# SmartSteirs_Base.net
KiCad netlist of a schematic drawn in EAGLE
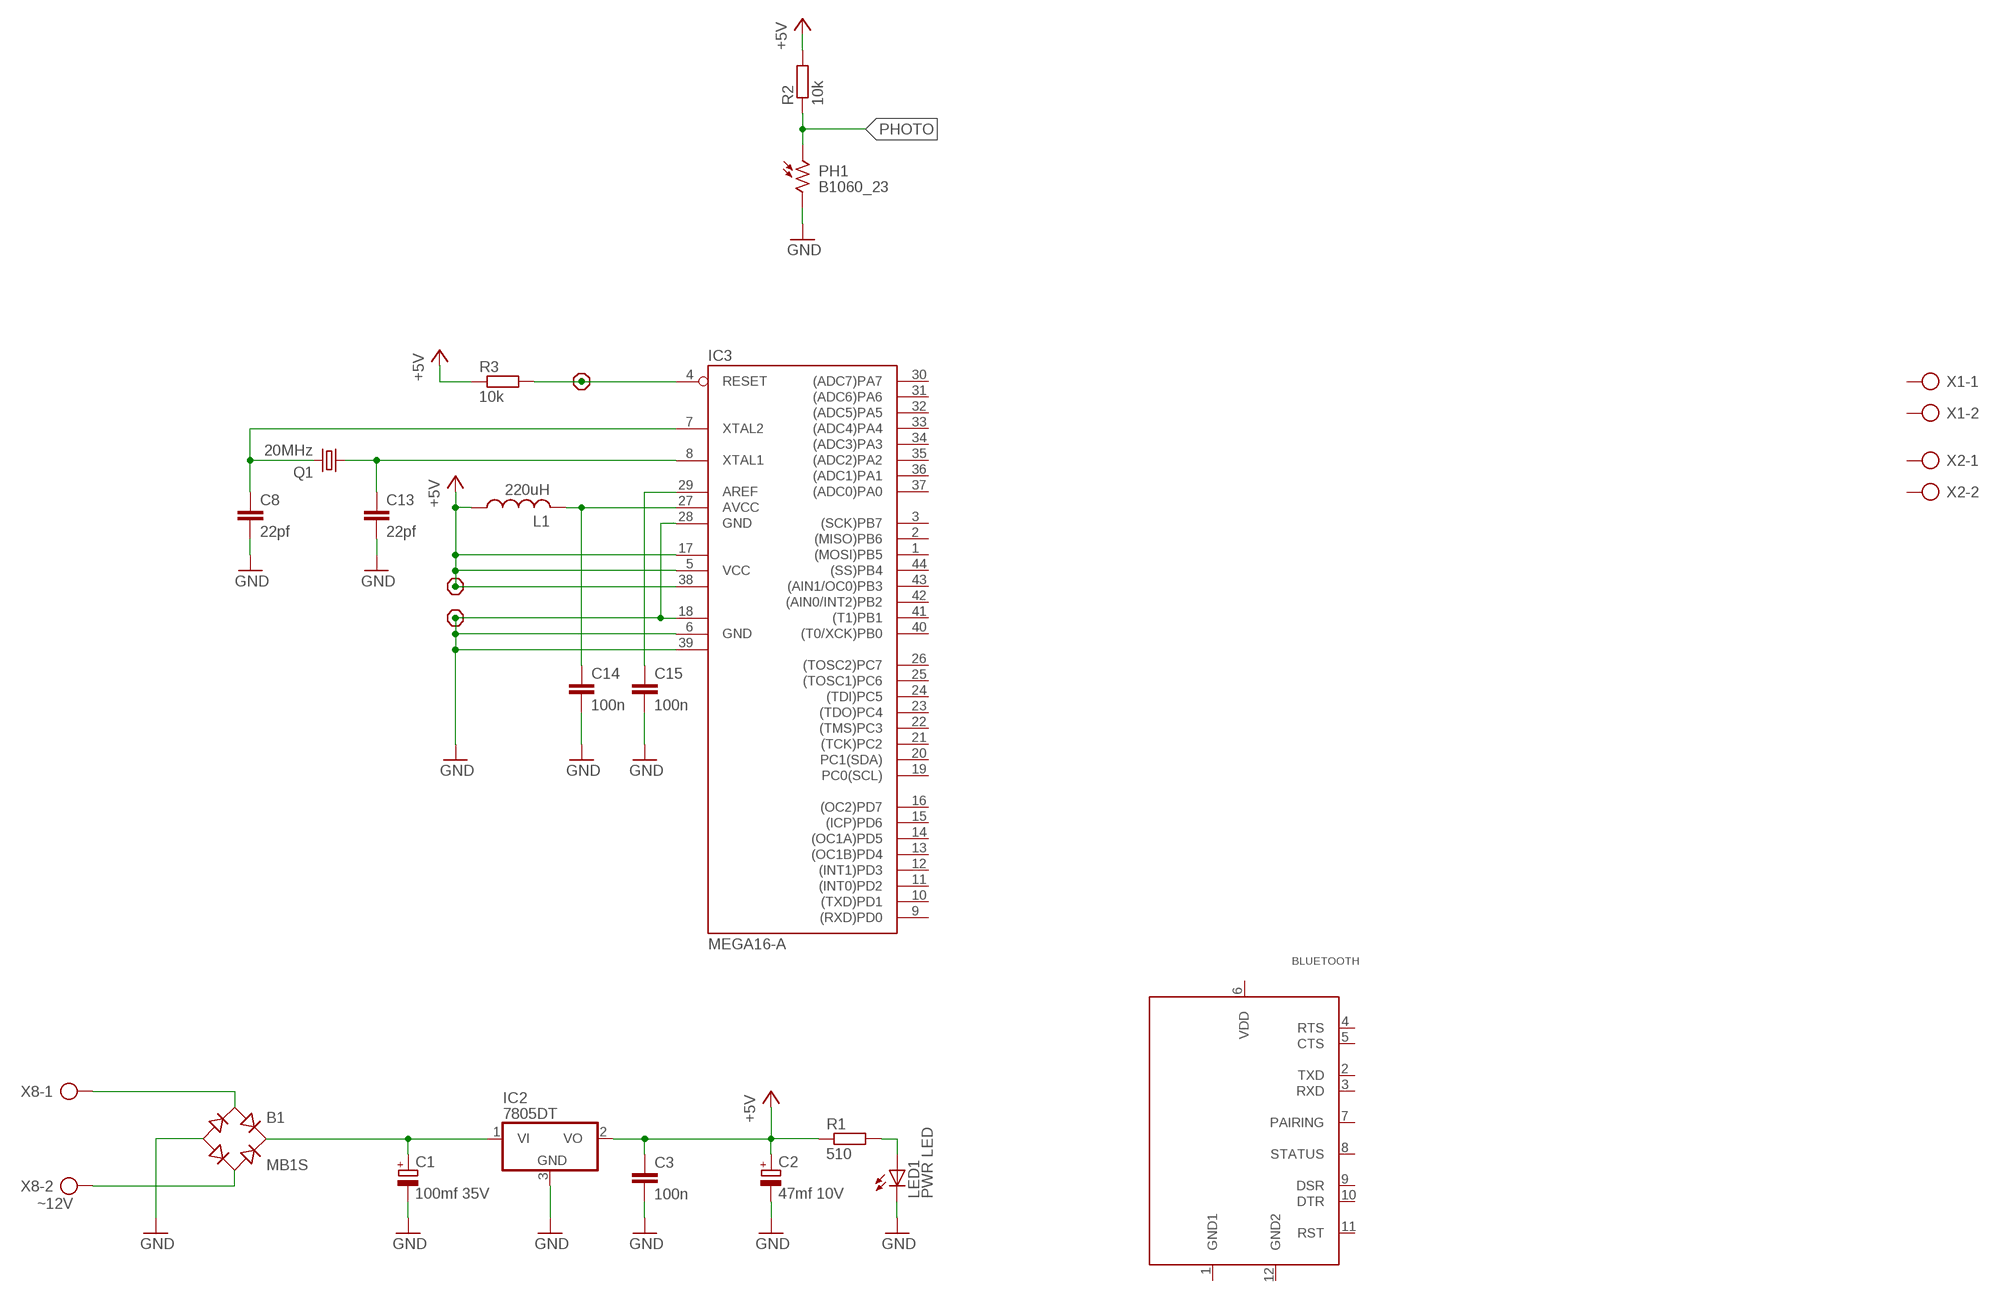
[diagram p0: schematic, sheet 1]

(export (version "E")
  (design (tool "Eeschema 10.0.6"))
  (components
    (comp (ref "B1")
      (value "MB1S")
      (footprint "eagle-import:SOIC-4")
      (libsource (lib "eagle-import") (part "MBS1"))
    )
    (comp (ref "BLUETOOTH")
      (value "ESD110ESD110")
      (footprint "eagle-import:ESD110")
      (libsource (lib "eagle-import") (part "ESD110ESD110"))
    )
    (comp (ref "C1")
      (value "100mf 35V")
      (footprint "eagle-import:E2,5-6")
      (libsource (lib "eagle-import") (part "CPOL-EUE2.5-6"))
    )
    (comp (ref "C2")
      (value "47mf 10V")
      (footprint "eagle-import:E2,5-6")
      (libsource (lib "eagle-import") (part "CPOL-EUE2.5-6"))
    )
    (comp (ref "C3")
      (value "100n")
      (footprint "eagle-import:C0805")
      (libsource (lib "eagle-import") (part "C-EUC0805"))
    )
    (comp (ref "C8")
      (value "22pf")
      (footprint "eagle-import:C0805")
      (libsource (lib "eagle-import") (part "C-EUC0805"))
    )
    (comp (ref "C13")
      (value "22pf")
      (footprint "eagle-import:C0805")
      (libsource (lib "eagle-import") (part "C-EUC0805"))
    )
    (comp (ref "C14")
      (value "100n")
      (footprint "eagle-import:C0805")
      (libsource (lib "eagle-import") (part "C-EUC0805"))
    )
    (comp (ref "C15")
      (value "100n")
      (footprint "eagle-import:C0805")
      (libsource (lib "eagle-import") (part "C-EUC0805"))
    )
    (comp (ref "IC2")
      (value "7805DT")
      (footprint "eagle-import:TO252")
      (libsource (lib "eagle-import") (part "78DT05"))
    )
    (comp (ref "IC3")
      (value "MEGA16-A")
      (footprint "eagle-import:TQFP44")
      (fields (field (name "MPN") "ATMEGA16-16AU"))
      (libsource (lib "eagle-import") (part "MEGA16-A"))
    )
    (comp (ref "JP13")
      (value "PIN_1")
      (footprint "eagle-import:1X01")
      (libsource (lib "eagle-import") (part "PIN_1"))
    )
    (comp (ref "JP14")
      (value "PIN_1")
      (footprint "eagle-import:1X01")
      (libsource (lib "eagle-import") (part "PIN_1"))
    )
    (comp (ref "JP15")
      (value "PIN_1")
      (footprint "eagle-import:1X01")
      (libsource (lib "eagle-import") (part "PIN_1"))
    )
    (comp (ref "L1")
      (value "220uH")
      (footprint "eagle-import:0207_5V")
      (libsource (lib "eagle-import") (part "L-US0207/5V"))
    )
    (comp (ref "LED1")
      (value "PWR LED")
      (footprint "eagle-import:LED3MM")
      (libsource (lib "eagle-import") (part "LED3MM"))
    )
    (comp (ref "PH1")
      (value "B1060_23")
      (footprint "eagle-import:TO-8_B10")
      (libsource (lib "eagle-import") (part "?1060B_23"))
    )
    (comp (ref "Q1")
      (value "20MHz")
      (footprint "eagle-import:HC49_S")
      (libsource (lib "eagle-import") (part "CRYSTALHC49S"))
    )
    (comp (ref "R1")
      (value "510")
      (footprint "eagle-import:M0805")
      (libsource (lib "eagle-import") (part "R-EU_M0805"))
    )
    (comp (ref "R2")
      (value "10k")
      (footprint "eagle-import:M0805")
      (libsource (lib "eagle-import") (part "R-EU_M0805"))
    )
    (comp (ref "R3")
      (value "10k")
      (footprint "eagle-import:M0805")
      (libsource (lib "eagle-import") (part "R-EU_M0805"))
    )
    (comp (ref "X1")
      (value "AK500/2")
      (footprint "eagle-import:AK500_2")
      (libsource (lib "eagle-import") (part "AK500/2"))
    )
    (comp (ref "X2")
      (value "AK500/2")
      (footprint "eagle-import:AK500_2")
      (libsource (lib "eagle-import") (part "AK500/2"))
    )
    (comp (ref "X8")
      (value "~12V")
      (footprint "eagle-import:AK500_2")
      (fields (field (name "OC_FARNELL") "unknown") (field (name "OC_NEWARK") "unknown"))
      (libsource (lib "eagle-import") (part "AK500/2"))
    )
  )
  (nets
    (net (code "1") (name "+5V") (class "Default")
      (node (ref "C2") (pin "+") (pinfunction "+_+") (pintype "passive"))
      (node (ref "C3") (pin "1") (pinfunction "1_1") (pintype "passive"))
      (node (ref "IC2") (pin "2") (pinfunction "VO_2") (pintype "passive"))
      (node (ref "IC3") (pin "17") (pinfunction "VCC1_17") (pintype "power_in"))
      (node (ref "IC3") (pin "38") (pinfunction "VCC2_38") (pintype "power_in"))
      (node (ref "IC3") (pin "5") (pinfunction "VCC_5") (pintype "power_in"))
      (node (ref "JP15") (pin "1") (pinfunction "P$1_1") (pintype "bidirectional"))
      (node (ref "L1") (pin "1") (pinfunction "1_1") (pintype "passive"))
      (node (ref "R1") (pin "1") (pinfunction "1_1") (pintype "passive"))
      (node (ref "R2") (pin "2") (pinfunction "2_2") (pintype "passive"))
      (node (ref "R3") (pin "1") (pinfunction "1_1") (pintype "passive"))
    )
    (net (code "2") (name "GND") (class "Default")
      (node (ref "B1") (pin "-") (pinfunction "-_-") (pintype "passive"))
      (node (ref "C1") (pin "-") (pinfunction "-_-") (pintype "passive"))
      (node (ref "C13") (pin "2") (pinfunction "2_2") (pintype "passive"))
      (node (ref "C14") (pin "2") (pinfunction "2_2") (pintype "passive"))
      (node (ref "C15") (pin "2") (pinfunction "2_2") (pintype "passive"))
      (node (ref "C2") (pin "-") (pinfunction "-_-") (pintype "passive"))
      (node (ref "C3") (pin "2") (pinfunction "2_2") (pintype "passive"))
      (node (ref "C8") (pin "2") (pinfunction "2_2") (pintype "passive"))
      (node (ref "IC2") (pin "3") (pinfunction "GND_3") (pintype "passive"))
      (node (ref "IC3") (pin "18") (pinfunction "GND1_18") (pintype "power_in"))
      (node (ref "IC3") (pin "28") (pinfunction "GND_28") (pintype "power_in"))
      (node (ref "IC3") (pin "39") (pinfunction "GND2_39") (pintype "power_in"))
      (node (ref "IC3") (pin "6") (pinfunction "GND_6") (pintype "power_in"))
      (node (ref "JP14") (pin "1") (pinfunction "P$1_1") (pintype "bidirectional"))
      (node (ref "LED1") (pin "K") (pinfunction "C_K") (pintype "passive"))
      (node (ref "PH1") (pin "2") (pinfunction "2_2") (pintype "passive"))
    )
    (net (code "3") (name "Net-(B1-AC1)") (class "Default")
      (node (ref "B1") (pin "~1") (pinfunction "AC1_~1") (pintype "passive"))
      (node (ref "X8") (pin "1") (pinfunction "KL_1") (pintype "passive"))
    )
    (net (code "4") (name "Net-(B1-AC2)") (class "Default")
      (node (ref "B1") (pin "~2") (pinfunction "AC2_~2") (pintype "passive"))
      (node (ref "X8") (pin "2") (pinfunction "KL_2") (pintype "passive"))
    )
    (net (code "5") (name "Net-(IC2-VI)") (class "Default")
      (node (ref "B1") (pin "+") (pinfunction "+_+") (pintype "passive"))
      (node (ref "C1") (pin "+") (pinfunction "+_+") (pintype "passive"))
      (node (ref "IC2") (pin "1") (pinfunction "VI_1") (pintype "input"))
    )
    (net (code "6") (name "Net-(IC3-AREF)") (class "Default")
      (node (ref "C15") (pin "1") (pinfunction "1_1") (pintype "passive"))
      (node (ref "IC3") (pin "29") (pinfunction "AREF_29") (pintype "passive"))
    )
    (net (code "7") (name "Net-(IC3-AVCC)") (class "Default")
      (node (ref "C14") (pin "1") (pinfunction "1_1") (pintype "passive"))
      (node (ref "IC3") (pin "27") (pinfunction "AVCC_27") (pintype "power_in"))
      (node (ref "L1") (pin "2") (pinfunction "2_2") (pintype "passive"))
    )
    (net (code "8") (name "Net-(IC3-RESET)") (class "Default")
      (node (ref "IC3") (pin "4") (pinfunction "RESET_4") (pintype "input"))
      (node (ref "JP13") (pin "1") (pinfunction "P$1_1") (pintype "bidirectional"))
      (node (ref "R3") (pin "2") (pinfunction "2_2") (pintype "passive"))
    )
    (net (code "9") (name "Net-(IC3-XTAL1)") (class "Default")
      (node (ref "C13") (pin "1") (pinfunction "1_1") (pintype "passive"))
      (node (ref "IC3") (pin "8") (pinfunction "XTAL1_8") (pintype "bidirectional"))
      (node (ref "Q1") (pin "1") (pinfunction "1_1") (pintype "passive"))
    )
    (net (code "10") (name "Net-(IC3-XTAL2)") (class "Default")
      (node (ref "C8") (pin "1") (pinfunction "1_1") (pintype "passive"))
      (node (ref "IC3") (pin "7") (pinfunction "XTAL2_7") (pintype "bidirectional"))
      (node (ref "Q1") (pin "2") (pinfunction "2_2") (pintype "passive"))
    )
    (net (code "11") (name "Net-(LED1-PadA)") (class "Default")
      (node (ref "LED1") (pin "A") (pinfunction "A_A") (pintype "passive"))
      (node (ref "R1") (pin "2") (pinfunction "2_2") (pintype "passive"))
    )
    (net (code "12") (name "PHOTO") (class "Default")
      (node (ref "PH1") (pin "1") (pinfunction "1_1") (pintype "passive"))
      (node (ref "R2") (pin "1") (pinfunction "1_1") (pintype "passive"))
    )
    (net (code "13") (name "unconnected-(BLUETOOTH-CTS-Pad5)") (class "Default")
      (node (ref "BLUETOOTH") (pin "5") (pinfunction "CTS_5") (pintype "passive"))
    )
    (net (code "14") (name "unconnected-(BLUETOOTH-DSR-Pad9)") (class "Default")
      (node (ref "BLUETOOTH") (pin "9") (pinfunction "DSR_9") (pintype "passive"))
    )
    (net (code "15") (name "unconnected-(BLUETOOTH-DTR-Pad10)") (class "Default")
      (node (ref "BLUETOOTH") (pin "10") (pinfunction "DTR_10") (pintype "passive"))
    )
    (net (code "16") (name "unconnected-(BLUETOOTH-GND1-Pad1)") (class "Default")
      (node (ref "BLUETOOTH") (pin "1") (pinfunction "GND1_1") (pintype "passive"))
    )
    (net (code "17") (name "unconnected-(BLUETOOTH-GND2-Pad12)") (class "Default")
      (node (ref "BLUETOOTH") (pin "12") (pinfunction "GND2_12") (pintype "passive"))
    )
    (net (code "18") (name "unconnected-(BLUETOOTH-PAIRING-Pad7)") (class "Default")
      (node (ref "BLUETOOTH") (pin "7") (pinfunction "PAIRING_7") (pintype "passive"))
    )
    (net (code "19") (name "unconnected-(BLUETOOTH-RST-Pad11)") (class "Default")
      (node (ref "BLUETOOTH") (pin "11") (pinfunction "RST_11") (pintype "passive"))
    )
    (net (code "20") (name "unconnected-(BLUETOOTH-RTS-Pad4)") (class "Default")
      (node (ref "BLUETOOTH") (pin "4") (pinfunction "RTS_4") (pintype "passive"))
    )
    (net (code "21") (name "unconnected-(BLUETOOTH-RXD-Pad3)") (class "Default")
      (node (ref "BLUETOOTH") (pin "3") (pinfunction "RXD_3") (pintype "passive"))
    )
    (net (code "22") (name "unconnected-(BLUETOOTH-STATUS-Pad8)") (class "Default")
      (node (ref "BLUETOOTH") (pin "8") (pinfunction "STATUS_8") (pintype "passive"))
    )
    (net (code "23") (name "unconnected-(BLUETOOTH-TXD-Pad2)") (class "Default")
      (node (ref "BLUETOOTH") (pin "2") (pinfunction "TXD_2") (pintype "passive"))
    )
    (net (code "24") (name "unconnected-(BLUETOOTH-VDD-Pad6)") (class "Default")
      (node (ref "BLUETOOTH") (pin "6") (pinfunction "VDD_6") (pintype "passive"))
    )
    (net (code "25") (name "unconnected-(IC3-(ADC0)PA0-Pad37)") (class "Default")
      (node (ref "IC3") (pin "37") (pinfunction "(ADC0)PA0_37") (pintype "bidirectional"))
    )
    (net (code "26") (name "unconnected-(IC3-(ADC1)PA1-Pad36)") (class "Default")
      (node (ref "IC3") (pin "36") (pinfunction "(ADC1)PA1_36") (pintype "bidirectional"))
    )
    (net (code "27") (name "unconnected-(IC3-(ADC2)PA2-Pad35)") (class "Default")
      (node (ref "IC3") (pin "35") (pinfunction "(ADC2)PA2_35") (pintype "bidirectional"))
    )
    (net (code "28") (name "unconnected-(IC3-(ADC3)PA3-Pad34)") (class "Default")
      (node (ref "IC3") (pin "34") (pinfunction "(ADC3)PA3_34") (pintype "bidirectional"))
    )
    (net (code "29") (name "unconnected-(IC3-(ADC4)PA4-Pad33)") (class "Default")
      (node (ref "IC3") (pin "33") (pinfunction "(ADC4)PA4_33") (pintype "bidirectional"))
    )
    (net (code "30") (name "unconnected-(IC3-(ADC5)PA5-Pad32)") (class "Default")
      (node (ref "IC3") (pin "32") (pinfunction "(ADC5)PA5_32") (pintype "bidirectional"))
    )
    (net (code "31") (name "unconnected-(IC3-(ADC6)PA6-Pad31)") (class "Default")
      (node (ref "IC3") (pin "31") (pinfunction "(ADC6)PA6_31") (pintype "bidirectional"))
    )
    (net (code "32") (name "unconnected-(IC3-(ADC7)PA7-Pad30)") (class "Default")
      (node (ref "IC3") (pin "30") (pinfunction "(ADC7)PA7_30") (pintype "bidirectional"))
    )
    (net (code "33") (name "unconnected-(IC3-(AIN0{slash}INT2)PB2-Pad42)") (class "Default")
      (node (ref "IC3") (pin "42") (pinfunction "(AIN0/INT2)PB2_42") (pintype "bidirectional"))
    )
    (net (code "34") (name "unconnected-(IC3-(AIN1{slash}OC0)PB3-Pad43)") (class "Default")
      (node (ref "IC3") (pin "43") (pinfunction "(AIN1/OC0)PB3_43") (pintype "bidirectional"))
    )
    (net (code "35") (name "unconnected-(IC3-(ICP)PD6-Pad15)") (class "Default")
      (node (ref "IC3") (pin "15") (pinfunction "(ICP)PD6_15") (pintype "bidirectional"))
    )
    (net (code "36") (name "unconnected-(IC3-(INT0)PD2-Pad11)") (class "Default")
      (node (ref "IC3") (pin "11") (pinfunction "(INT0)PD2_11") (pintype "bidirectional"))
    )
    (net (code "37") (name "unconnected-(IC3-(INT1)PD3-Pad12)") (class "Default")
      (node (ref "IC3") (pin "12") (pinfunction "(INT1)PD3_12") (pintype "bidirectional"))
    )
    (net (code "38") (name "unconnected-(IC3-(MISO)PB6-Pad2)") (class "Default")
      (node (ref "IC3") (pin "2") (pinfunction "(MISO)PB6_2") (pintype "bidirectional"))
    )
    (net (code "39") (name "unconnected-(IC3-(MOSI)PB5-Pad1)") (class "Default")
      (node (ref "IC3") (pin "1") (pinfunction "(MOSI)PB5_1") (pintype "bidirectional"))
    )
    (net (code "40") (name "unconnected-(IC3-(OC1A)PD5-Pad14)") (class "Default")
      (node (ref "IC3") (pin "14") (pinfunction "(OC1A)PD5_14") (pintype "bidirectional"))
    )
    (net (code "41") (name "unconnected-(IC3-(OC1B)PD4-Pad13)") (class "Default")
      (node (ref "IC3") (pin "13") (pinfunction "(OC1B)PD4_13") (pintype "bidirectional"))
    )
    (net (code "42") (name "unconnected-(IC3-(OC2)PD7-Pad16)") (class "Default")
      (node (ref "IC3") (pin "16") (pinfunction "(OC2)PD7_16") (pintype "bidirectional"))
    )
    (net (code "43") (name "unconnected-(IC3-(RXD)PD0-Pad9)") (class "Default")
      (node (ref "IC3") (pin "9") (pinfunction "(RXD)PD0_9") (pintype "bidirectional"))
    )
    (net (code "44") (name "unconnected-(IC3-(SCK)PB7-Pad3)") (class "Default")
      (node (ref "IC3") (pin "3") (pinfunction "(SCK)PB7_3") (pintype "bidirectional"))
    )
    (net (code "45") (name "unconnected-(IC3-(SS)PB4-Pad44)") (class "Default")
      (node (ref "IC3") (pin "44") (pinfunction "(SS)PB4_44") (pintype "bidirectional"))
    )
    (net (code "46") (name "unconnected-(IC3-(T0{slash}XCK)PB0-Pad40)") (class "Default")
      (node (ref "IC3") (pin "40") (pinfunction "(T0/XCK)PB0_40") (pintype "bidirectional"))
    )
    (net (code "47") (name "unconnected-(IC3-(T1)PB1-Pad41)") (class "Default")
      (node (ref "IC3") (pin "41") (pinfunction "(T1)PB1_41") (pintype "bidirectional"))
    )
    (net (code "48") (name "unconnected-(IC3-(TCK)PC2-Pad21)") (class "Default")
      (node (ref "IC3") (pin "21") (pinfunction "(TCK)PC2_21") (pintype "bidirectional"))
    )
    (net (code "49") (name "unconnected-(IC3-(TDI)PC5-Pad24)") (class "Default")
      (node (ref "IC3") (pin "24") (pinfunction "(TDI)PC5_24") (pintype "bidirectional"))
    )
    (net (code "50") (name "unconnected-(IC3-(TDO)PC4-Pad23)") (class "Default")
      (node (ref "IC3") (pin "23") (pinfunction "(TDO)PC4_23") (pintype "bidirectional"))
    )
    (net (code "51") (name "unconnected-(IC3-(TMS)PC3-Pad22)") (class "Default")
      (node (ref "IC3") (pin "22") (pinfunction "(TMS)PC3_22") (pintype "bidirectional"))
    )
    (net (code "52") (name "unconnected-(IC3-(TOSC1)PC6-Pad25)") (class "Default")
      (node (ref "IC3") (pin "25") (pinfunction "(TOSC1)PC6_25") (pintype "bidirectional"))
    )
    (net (code "53") (name "unconnected-(IC3-(TOSC2)PC7-Pad26)") (class "Default")
      (node (ref "IC3") (pin "26") (pinfunction "(TOSC2)PC7_26") (pintype "bidirectional"))
    )
    (net (code "54") (name "unconnected-(IC3-(TXD)PD1-Pad10)") (class "Default")
      (node (ref "IC3") (pin "10") (pinfunction "(TXD)PD1_10") (pintype "bidirectional"))
    )
    (net (code "55") (name "unconnected-(IC3-PC0(SCL)-Pad19)") (class "Default")
      (node (ref "IC3") (pin "19") (pinfunction "PC0(SCL)_19") (pintype "bidirectional"))
    )
    (net (code "56") (name "unconnected-(IC3-PC1(SDA)-Pad20)") (class "Default")
      (node (ref "IC3") (pin "20") (pinfunction "PC1(SDA)_20") (pintype "bidirectional"))
    )
    (net (code "57") (name "unconnected-(X1A-KL-Pad1)") (class "Default")
      (node (ref "X1") (pin "1") (pinfunction "KL_1") (pintype "passive"))
    )
    (net (code "58") (name "unconnected-(X1B-KL-Pad2)") (class "Default")
      (node (ref "X1") (pin "2") (pinfunction "KL_2") (pintype "passive"))
    )
    (net (code "59") (name "unconnected-(X2A-KL-Pad1)") (class "Default")
      (node (ref "X2") (pin "1") (pinfunction "KL_1") (pintype "passive"))
    )
    (net (code "60") (name "unconnected-(X2B-KL-Pad2)") (class "Default")
      (node (ref "X2") (pin "2") (pinfunction "KL_2") (pintype "passive"))
    )
  )
)
